# HV_Diffuser.net
KiCad netlist of a schematic drawn in Altium Designer
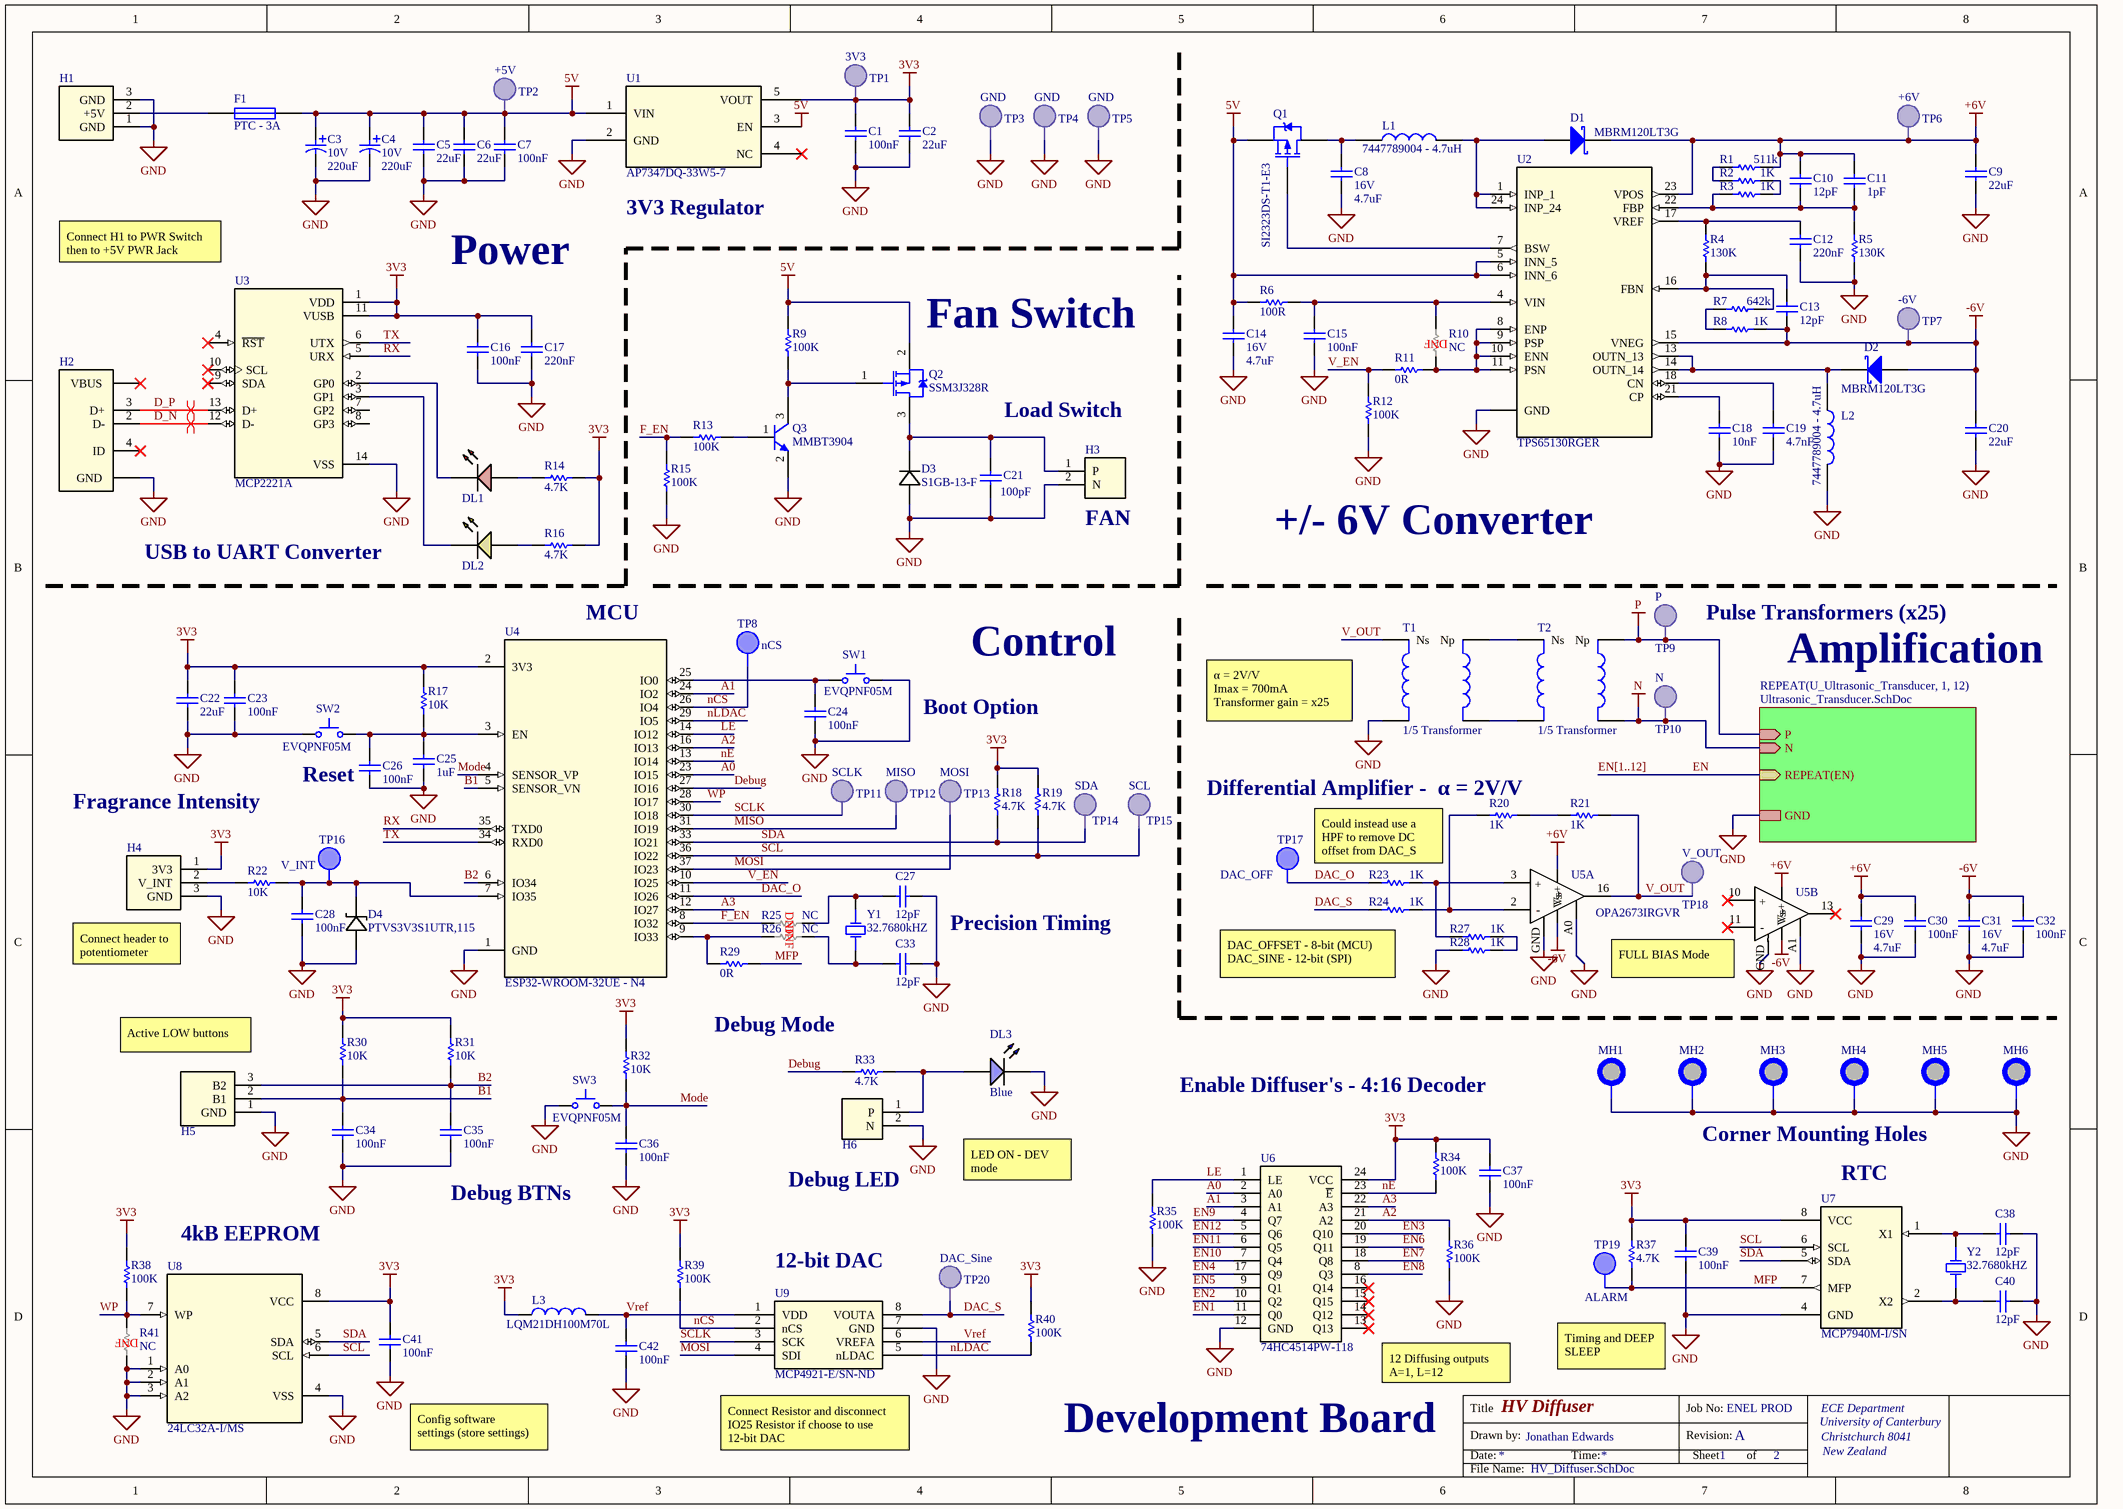
[diagram p0: HV_Diffuser.SchDoc]

(export (version "E")
  (design (tool "Eeschema 10.0.6"))
  (components
    (comp (ref "C1")
      (value "100nF")
      (footprint "C_0603")
      (description "CAP CER 0.1uF 50V X7R 0603")
      (libsource (lib "Diffuser") (part "CC_100nF"))
    )
    (comp (ref "C2")
      (value "22uF")
      (footprint "C_0805")
      (description "CAP CER 22UF 10V X5R 0805")
      (libsource (lib "Diffuser") (part "CC_22uF"))
    )
    (comp (ref "C3")
      (value "220uF")
      (footprint "C_2917")
      (description "100 µF Molded Tantalum Capacitors 16 V 2917 (7343 Metric) 75mOhm")
      (fields (field (name "VOLTAGE") "10V"))
      (libsource (lib "Diffuser") (part "CC_100uF"))
    )
    (comp (ref "C4")
      (value "220uF")
      (footprint "C_2917")
      (description "100 µF Molded Tantalum Capacitors 16 V 2917 (7343 Metric) 75mOhm")
      (fields (field (name "VOLTAGE") "10V"))
      (libsource (lib "Diffuser") (part "CC_100uF"))
    )
    (comp (ref "C5")
      (value "22uF")
      (footprint "C_0805")
      (description "CAP CER 22UF 10V X5R 0805")
      (libsource (lib "Diffuser") (part "CC_22uF"))
    )
    (comp (ref "C6")
      (value "22uF")
      (footprint "C_0805")
      (description "CAP CER 22UF 10V X5R 0805")
      (libsource (lib "Diffuser") (part "CC_22uF"))
    )
    (comp (ref "C7")
      (value "100nF")
      (footprint "C_0603")
      (description "CAP CER 0.1uF 50V X7R 0603")
      (libsource (lib "Diffuser") (part "CC_100nF"))
    )
    (comp (ref "C8")
      (value "4.7uF")
      (footprint "C_0805")
      (description "4.7 µF ±10% 50V Ceramic Capacitor X7R 0805 (2012 Metric)")
      (fields (field (name "VOLTAGE") "16V"))
      (libsource (lib "Diffuser") (part "CC_4.7uF_50V"))
    )
    (comp (ref "C9")
      (value "22uF")
      (footprint "C_0805")
      (description "CAP CER 22UF 10V X5R 0805")
      (libsource (lib "Diffuser") (part "CC_22uF"))
    )
    (comp (ref "C10")
      (value "12pF")
      (footprint "C_0603")
      (description "CAP CER 0.220uF 50V X7R 0603")
      (libsource (lib "Diffuser") (part "CC_220nF"))
    )
    (comp (ref "C11")
      (value "1pF")
      (footprint "C_0603")
      (description "CAP CER 1pF 50V X7R 0603")
      (libsource (lib "Diffuser") (part "CC_220nF"))
    )
    (comp (ref "C12")
      (value "220nF")
      (footprint "C_0603")
      (description "CAP CER 0.220uF 50V X7R 0603")
      (libsource (lib "Diffuser") (part "CC_220nF"))
    )
    (comp (ref "C13")
      (value "12pF")
      (footprint "C_0603")
      (description "CAP CER 0.220uF 50V X7R 0603")
      (libsource (lib "Diffuser") (part "CC_220nF"))
    )
    (comp (ref "C14")
      (value "4.7uF")
      (footprint "C_0805")
      (description "4.7 µF ±10% 50V Ceramic Capacitor X7R 0805 (2012 Metric)")
      (fields (field (name "VOLTAGE") "16V"))
      (libsource (lib "Diffuser") (part "CC_4.7uF_50V"))
    )
    (comp (ref "C15")
      (value "100nF")
      (footprint "C_0603")
      (description "CAP CER 0.1uF 50V X7R 0603")
      (libsource (lib "Diffuser") (part "CC_100nF"))
    )
    (comp (ref "C16")
      (value "100nF")
      (footprint "C_0603")
      (description "CAP CER 0.1uF 50V X7R 0603")
      (libsource (lib "Diffuser") (part "CC_100nF"))
    )
    (comp (ref "C17")
      (value "220nF")
      (footprint "C_0603")
      (description "CAP CER 0.220uF 50V X7R 0603")
      (libsource (lib "Diffuser") (part "CC_220nF"))
    )
    (comp (ref "C18")
      (value "10nF")
      (footprint "C_0603")
      (description "CAP CER 0.1uF 50V X7R 0603")
      (libsource (lib "Diffuser") (part "CC_100nF"))
    )
    (comp (ref "C19")
      (value "4.7nF")
      (footprint "C_0603")
      (description "CAP CER 4.7nF 50V X7R 0603")
      (libsource (lib "Diffuser") (part "CC_4.7nF"))
    )
    (comp (ref "C20")
      (value "22uF")
      (footprint "C_0805")
      (description "CAP CER 22UF 10V X5R 0805")
      (libsource (lib "Diffuser") (part "CC_22uF"))
    )
    (comp (ref "C21")
      (value "100pF")
      (footprint "C_0603")
      (description "CAP CER 100pF 50V C0G/NP0 0603")
      (fields (field (name "VOLTAGE") "50V"))
      (libsource (lib "Diffuser") (part "CC_100pF"))
    )
    (comp (ref "C22")
      (value "22uF")
      (footprint "C_0805")
      (description "CAP CER 22UF 10V X5R 0805")
      (libsource (lib "Diffuser") (part "CC_22uF"))
    )
    (comp (ref "C23")
      (value "100nF")
      (footprint "C_0603")
      (description "CAP CER 0.1uF 50V X7R 0603")
      (libsource (lib "Diffuser") (part "CC_100nF"))
    )
    (comp (ref "C24")
      (value "100nF")
      (footprint "C_0603")
      (description "CAP CER 0.1uF 50V X7R 0603")
      (libsource (lib "Diffuser") (part "CC_100nF"))
    )
    (comp (ref "C25")
      (value "1uF")
      (footprint "C_0603")
      (description "CAP CER 1uF 16V X7R 0603")
      (libsource (lib "Diffuser") (part "CC_1uF"))
    )
    (comp (ref "C26")
      (value "100nF")
      (footprint "C_0603")
      (description "CAP CER 0.1uF 50V X7R 0603")
      (libsource (lib "Diffuser") (part "CC_100nF"))
    )
    (comp (ref "C27")
      (value "12pF")
      (footprint "C_0603")
      (description "CAP CER 0.220uF 50V X7R 0603")
      (libsource (lib "Diffuser") (part "CC_220nF"))
    )
    (comp (ref "C28")
      (value "100nF")
      (footprint "C_0603")
      (description "CAP CER 0.1uF 50V X7R 0603")
      (libsource (lib "Diffuser") (part "CC_100nF"))
    )
    (comp (ref "C29")
      (value "4.7uF")
      (footprint "C_0805")
      (description "4.7 µF ±10% 50V Ceramic Capacitor X7R 0805 (2012 Metric)")
      (fields (field (name "VOLTAGE") "16V"))
      (libsource (lib "Diffuser") (part "CC_4.7uF_50V"))
    )
    (comp (ref "C30")
      (value "100nF")
      (footprint "C_0603")
      (description "CAP CER 0.1uF 50V X7R 0603")
      (libsource (lib "Diffuser") (part "CC_100nF"))
    )
    (comp (ref "C31")
      (value "4.7uF")
      (footprint "C_0805")
      (description "4.7 µF ±10% 50V Ceramic Capacitor X7R 0805 (2012 Metric)")
      (fields (field (name "VOLTAGE") "16V"))
      (libsource (lib "Diffuser") (part "CC_4.7uF_50V"))
    )
    (comp (ref "C32")
      (value "100nF")
      (footprint "C_0603")
      (description "CAP CER 0.1uF 50V X7R 0603")
      (libsource (lib "Diffuser") (part "CC_100nF"))
    )
    (comp (ref "C33")
      (value "12pF")
      (footprint "C_0603")
      (description "CAP CER 0.220uF 50V X7R 0603")
      (libsource (lib "Diffuser") (part "CC_220nF"))
    )
    (comp (ref "C34")
      (value "100nF")
      (footprint "C_0603")
      (description "CAP CER 0.1uF 50V X7R 0603")
      (libsource (lib "Diffuser") (part "CC_100nF"))
    )
    (comp (ref "C35")
      (value "100nF")
      (footprint "C_0603")
      (description "CAP CER 0.1uF 50V X7R 0603")
      (libsource (lib "Diffuser") (part "CC_100nF"))
    )
    (comp (ref "C36")
      (value "100nF")
      (footprint "C_0603")
      (description "CAP CER 0.1uF 50V X7R 0603")
      (libsource (lib "Diffuser") (part "CC_100nF"))
    )
    (comp (ref "C37")
      (value "100nF")
      (footprint "C_0603")
      (description "CAP CER 0.1uF 50V X7R 0603")
      (libsource (lib "Diffuser") (part "CC_100nF"))
    )
    (comp (ref "C38")
      (value "12pF")
      (footprint "C_0603")
      (description "CAP CER 0.220uF 50V X7R 0603")
      (libsource (lib "Diffuser") (part "CC_220nF"))
    )
    (comp (ref "C39")
      (value "100nF")
      (footprint "C_0603")
      (description "CAP CER 0.1uF 50V X7R 0603")
      (libsource (lib "Diffuser") (part "CC_100nF"))
    )
    (comp (ref "C40")
      (value "12pF")
      (footprint "C_0603")
      (description "CAP CER 0.220uF 50V X7R 0603")
      (libsource (lib "Diffuser") (part "CC_220nF"))
    )
    (comp (ref "C41")
      (value "100nF")
      (footprint "C_0603")
      (description "CAP CER 0.1uF 50V X7R 0603")
      (libsource (lib "Diffuser") (part "CC_100nF"))
    )
    (comp (ref "C42")
      (value "100nF")
      (footprint "C_0603")
      (description "CAP CER 0.1uF 50V X7R 0603")
      (libsource (lib "Diffuser") (part "CC_100nF"))
    )
    (comp (ref "D1")
      (value "MBRM120LT3G")
      (footprint "DO-216AA")
      (description "Diode 20 V 1A Surface Mount Powermite")
      (fields (field (name "COPYRIGHT") "Copyright (C) 2024 Ultra Librarian. All rights reserved."))
      (libsource (lib "Diffuser") (part "MBRM120LT3G"))
    )
    (comp (ref "D2")
      (value "MBRM120LT3G")
      (footprint "DO-216AA")
      (description "Diode 20 V 1A Surface Mount Powermite")
      (fields (field (name "COPYRIGHT") "Copyright (C) 2024 Ultra Librarian. All rights reserved."))
      (libsource (lib "Diffuser") (part "MBRM120LT3G"))
    )
    (comp (ref "D3")
      (value "S1GB-13-F")
      (footprint "DO-214AA, SMB")
      (description "Diode 400 V 1A Surface Mount SMB")
      (libsource (lib "Diffuser") (part "S1GB-13-F"))
    )
    (comp (ref "D4")
      (value "PTVS3V3S1UTR,115")
      (footprint "CR_PTVS3V_NEX-M")
      (description "8V Clamp 43.8A Ipp Tvs Diode Surface Mount SOD-123W")
      (fields (field (name "COPYRIGHT") "Copyright (C) 2023 Ultra Librarian. All rights reserved."))
      (libsource (lib "Diffuser") (part "PTVS3V3S1UTR,115"))
    )
    (comp (ref "DL1")
      (value "Red")
      (footprint "WL-SMCW0603")
      (description "LED Red 250mcd 0603 SMD")
      (libsource (lib "Diffuser") (part "Leds - 150060RS75000"))
    )
    (comp (ref "DL2")
      (value "Yellow")
      (footprint "WL-SMCW0603")
      (description "LED Yellow 120mcd 0603 SMD")
      (libsource (lib "Diffuser") (part "Leds - 150060YS75000"))
    )
    (comp (ref "DL3")
      (value "Blue")
      (footprint "WL-SMCW0603")
      (description "LED Blue 270mcd 0603 SMD")
      (fields (field (name "LED COLOUR") "Blue"))
      (libsource (lib "Diffuser") (part "Leds - 150060BS75000"))
    )
    (comp (ref "F1")
      (value "PTC - 3A")
      (footprint "PTC_Fuse_1812")
      (description "PTC RESET FUSE 3.0A 24V 1812")
      (libsource (lib "Diffuser") (part "FS_PTC_Fuse_3A"))
    )
    (comp (ref "H1")
      (value "3 pin - 2mm")
      (footprint "TE_440054-3")
      (description "2.0MM,HDR,3POS,VERTICAL")
      (fields (field (name "MP") "440054-3") (field (name "MF") "TE Connectivity"))
      (libsource (lib "Diffuser") (part "440054-3"))
    )
    (comp (ref "H2")
      (value "JS_USB_MICRO_B")
      (footprint "JS_USB_MICRO_B")
      (description "CONN USB MICRO B RECPT SMT R/A")
      (fields (field (name "MANUFACTURER") "FCI") (field (name "MANUFACTURER PART NUMBER") "10118194-0001LF"))
      (libsource (lib "Diffuser") (part "JS_USB_MICRO_B_SMT"))
    )
    (comp (ref "H3")
      (value "2 Pin Male 2mm")
      (footprint "JST_B2B-PH-K-S")
      (description "CONN HDR 2POS 0.1 TIN PCB")
      (libsource (lib "") (part "2 Pin Male 2mm_1"))
    )
    (comp (ref "H4")
      (value "3 pin - 2mm")
      (footprint "TE_440054-3")
      (description "2.0MM,HDR,3POS,VERTICAL")
      (fields (field (name "MP") "440054-3") (field (name "MF") "TE Connectivity"))
      (libsource (lib "") (part "440054-3_1"))
    )
    (comp (ref "H5")
      (value "3 pin - 2mm")
      (footprint "TE_440054-3")
      (description "2.0MM,HDR,3POS,VERTICAL")
      (fields (field (name "MP") "440054-3") (field (name "MF") "TE Connectivity"))
      (libsource (lib "Diffuser") (part "440054-3"))
    )
    (comp (ref "H6")
      (value "2 Pin Male 2mm")
      (footprint "JST_B2B-PH-K-S")
      (description "CONN HDR 2POS 0.1 TIN PCB")
      (libsource (lib "Diffuser") (part "2 Pin Male 2mm"))
    )
    (comp (ref "L1")
      (value "7447789004 - 4.7uH")
      (footprint "7447789004 - 4.7uH")
      (description "4.7 µH Shielded Drum Core, Wirewound Inductor 2.9 A 35mOhm Max Nonstandard")
      (libsource (lib "Diffuser") (part "7447789004 - 4.7uH"))
    )
    (comp (ref "L2")
      (value "7447789004 - 4.7uH")
      (footprint "7447789004 - 4.7uH")
      (description "4.7 µH Shielded Drum Core, Wirewound Inductor 2.9 A 35mOhm Max Nonstandard")
      (libsource (lib "") (part "7447789004 - 4.7uH_1"))
    )
    (comp (ref "L3")
      (value "LQM21DH100M70L")
      (footprint "R_0805")
      (description "Inductor with Inductance: 10uH Tol. +/-20%, Package: 0805 (2012)")
      (libsource (lib "Diffuser") (part "10uH - LQM21DH100M70L"))
    )
    (comp (ref "MH1")
      (value "MH_M2")
      (footprint "MH_M2")
      (description "Mounting Holes")
      (libsource (lib "Diffuser") (part "MH_M2"))
    )
    (comp (ref "MH2")
      (value "MH_M2")
      (footprint "MH_M2")
      (description "Mounting Holes")
      (libsource (lib "Diffuser") (part "MH_M2"))
    )
    (comp (ref "MH3")
      (value "MH_M2")
      (footprint "MH_M2")
      (description "Mounting Holes")
      (libsource (lib "Diffuser") (part "MH_M2"))
    )
    (comp (ref "MH4")
      (value "MH_M2")
      (footprint "MH_M2")
      (description "Mounting Holes")
      (libsource (lib "Diffuser") (part "MH_M2"))
    )
    (comp (ref "MH5")
      (value "MH_M2")
      (footprint "MH_M2")
      (description "Mounting Holes")
      (libsource (lib "Diffuser") (part "MH_M2"))
    )
    (comp (ref "MH6")
      (value "MH_M2")
      (footprint "MH_M2")
      (description "Mounting Holes")
      (libsource (lib "Diffuser") (part "MH_M2"))
    )
    (comp (ref "Q1")
      (value "SI2323DS-T1-E3")
      (footprint "SOT23")
      (description "P-Channel 20V 3.7A _Ta_ 750mW _Ta_ Surface Mount SOT-23-3 _TO-236_")
      (fields (field (name "MF") "Vishay Siliconix"))
      (libsource (lib "Diffuser") (part "SI2323DS-T1-E3"))
    )
    (comp (ref "Q2")
      (value "SSM3J328R")
      (footprint "SOT-23F")
      (description "MOSFET P-CH 20V 6A SOT23F")
      (libsource (lib "Diffuser") (part "P Mos - SSM3J328R"))
    )
    (comp (ref "Q3")
      (value "MMBT3904")
      (footprint "SOT23_NXP-M")
      (description "TRANS NPN 40V 200MA TO236AB")
      (fields (field (name "MANUFACTURER") "NXP"))
      (libsource (lib "Diffuser") (part "NPN - MMBT3904"))
    )
    (comp (ref "R1")
      (value "511k")
      (footprint "R_0603")
      (description "RES 512K OHM 0.1% 1/10W 0603")
      (libsource (lib "Diffuser") (part "RS_100K"))
    )
    (comp (ref "R2")
      (value "1K")
      (footprint "R_0603")
      (description "RES 1K OHM 0.1% 1/10W 0603")
      (libsource (lib "Diffuser") (part "RS_1K"))
    )
    (comp (ref "R3")
      (value "1K")
      (footprint "R_0603")
      (description "RES 1K OHM 0.1% 1/10W 0603")
      (libsource (lib "Diffuser") (part "RS_1K"))
    )
    (comp (ref "R4")
      (value "130K")
      (footprint "R_0603")
      (description "RES 130K OHM 0.1% 1/10W 0603")
      (libsource (lib "Diffuser") (part "RS_1K"))
    )
    (comp (ref "R5")
      (value "130K")
      (footprint "R_0603")
      (description "RES 130K OHM 0.1% 1/10W 0603")
      (libsource (lib "Diffuser") (part "RS_1K"))
    )
    (comp (ref "R6")
      (value "100R")
      (footprint "R_0603")
      (description "100 Ohms ±0.1% 0.167W, 1/6W Chip Resistor 0603 (1608 Metric) Thin Film")
      (libsource (lib "Diffuser") (part "RS_0R"))
    )
    (comp (ref "R7")
      (value "642k")
      (footprint "R_0603")
      (description "RES 100K OHM 1% 1/10W 0603")
      (libsource (lib "Diffuser") (part "RS_100K"))
    )
    (comp (ref "R8")
      (value "1K")
      (footprint "R_0603")
      (description "RES 1K OHM 0.1% 1/10W 0603")
      (libsource (lib "Diffuser") (part "RS_1K"))
    )
    (comp (ref "R9")
      (value "100K")
      (footprint "R_0603")
      (description "RES 100K OHM 1% 1/10W 0603")
      (libsource (lib "Diffuser") (part "RS_100K"))
    )
    (comp (ref "R10")
      (value "NC")
      (footprint "R_0603_NC")
      (description "NC - 0603")
      (libsource (lib "Diffuser") (part "RS_NC"))
    )
    (comp (ref "R11")
      (value "0R")
      (footprint "R_0603")
      (description "RES SMD 0 OHM JUMPER 1/10W 0603")
      (libsource (lib "Diffuser") (part "RS_0R"))
    )
    (comp (ref "R12")
      (value "100K")
      (footprint "R_0603")
      (description "RES 100K OHM 1% 1/10W 0603")
      (libsource (lib "Diffuser") (part "RS_100K"))
    )
    (comp (ref "R13")
      (value "100K")
      (footprint "R_0603")
      (description "RES 100K OHM 1% 1/10W 0603")
      (libsource (lib "Diffuser") (part "RS_100K"))
    )
    (comp (ref "R14")
      (value "4.7K")
      (footprint "R_0603")
      (description "RES SMD 4.7K OHM 1% 1/10W 0603")
      (libsource (lib "Diffuser") (part "RS_4.7K"))
    )
    (comp (ref "R15")
      (value "100K")
      (footprint "R_0603")
      (description "RES 100K OHM 1% 1/10W 0603")
      (libsource (lib "Diffuser") (part "RS_100K"))
    )
    (comp (ref "R16")
      (value "4.7K")
      (footprint "R_0603")
      (description "RES SMD 4.7K OHM 1% 1/10W 0603")
      (libsource (lib "Diffuser") (part "RS_4.7K"))
    )
    (comp (ref "R17")
      (value "10K")
      (footprint "R_0603")
      (description "RES SMD 10K OHM 1% 1/10W 0603")
      (libsource (lib "Diffuser") (part "RS_10K"))
    )
    (comp (ref "R18")
      (value "4.7K")
      (footprint "R_0603")
      (description "RES SMD 4.7K OHM 1% 1/10W 0603")
      (libsource (lib "Diffuser") (part "RS_4.7K"))
    )
    (comp (ref "R19")
      (value "4.7K")
      (footprint "R_0603")
      (description "RES SMD 4.7K OHM 1% 1/10W 0603")
      (libsource (lib "Diffuser") (part "RS_4.7K"))
    )
    (comp (ref "R20")
      (value "1K")
      (footprint "R_0603")
      (description "RES 1K OHM 1% 1/10W 0603")
      (libsource (lib "Diffuser") (part "RS_1K"))
    )
    (comp (ref "R21")
      (value "1K")
      (footprint "R_0603")
      (description "RES 1K OHM 1% 1/10W 0603")
      (libsource (lib "Diffuser") (part "RS_1K"))
    )
    (comp (ref "R22")
      (value "10K")
      (footprint "R_0603")
      (description "RES SMD 10K OHM 1% 1/10W 0603")
      (libsource (lib "Diffuser") (part "RS_10K"))
    )
    (comp (ref "R23")
      (value "1K")
      (footprint "R_0603")
      (description "RES 1K OHM 1% 1/10W 0603")
      (libsource (lib "Diffuser") (part "RS_1K"))
    )
    (comp (ref "R24")
      (value "1K")
      (footprint "R_0603")
      (description "RES 1K OHM 1% 1/10W 0603")
      (libsource (lib "Diffuser") (part "RS_1K"))
    )
    (comp (ref "R25")
      (value "NC")
      (footprint "R_0603_NC")
      (description "NC - 0603")
      (libsource (lib "Diffuser") (part "RS_NC"))
    )
    (comp (ref "R26")
      (value "NC")
      (footprint "R_0603_NC")
      (description "NC - 0603")
      (libsource (lib "Diffuser") (part "RS_NC"))
    )
    (comp (ref "R27")
      (value "1K")
      (footprint "R_0603")
      (description "RES 1K OHM 1% 1/10W 0603")
      (libsource (lib "Diffuser") (part "RS_1K"))
    )
    (comp (ref "R28")
      (value "1K")
      (footprint "R_0603")
      (description "RES 1K OHM 1% 1/10W 0603")
      (libsource (lib "Diffuser") (part "RS_1K"))
    )
    (comp (ref "R29")
      (value "0R")
      (footprint "R_0603")
      (description "RES SMD 0 OHM JUMPER 1/10W 0603")
      (libsource (lib "Diffuser") (part "RS_0R"))
    )
    (comp (ref "R30")
      (value "10K")
      (footprint "R_0603")
      (description "RES SMD 10K OHM 1% 1/10W 0603")
      (libsource (lib "Diffuser") (part "RS_10K"))
    )
    (comp (ref "R31")
      (value "10K")
      (footprint "R_0603")
      (description "RES SMD 10K OHM 1% 1/10W 0603")
      (libsource (lib "Diffuser") (part "RS_10K"))
    )
    (comp (ref "R32")
      (value "10K")
      (footprint "R_0603")
      (description "RES SMD 10K OHM 1% 1/10W 0603")
      (libsource (lib "Diffuser") (part "RS_10K"))
    )
    (comp (ref "R33")
      (value "4.7K")
      (footprint "R_0603")
      (description "RES SMD 4.7K OHM 1% 1/10W 0603")
      (libsource (lib "Diffuser") (part "RS_4.7K"))
    )
    (comp (ref "R34")
      (value "100K")
      (footprint "R_0603")
      (description "RES 100K OHM 1% 1/10W 0603")
      (libsource (lib "Diffuser") (part "RS_100K"))
    )
    (comp (ref "R35")
      (value "100K")
      (footprint "R_0603")
      (description "RES 100K OHM 1% 1/10W 0603")
      (libsource (lib "Diffuser") (part "RS_100K"))
    )
    (comp (ref "R36")
      (value "100K")
      (footprint "R_0603")
      (description "RES 100K OHM 1% 1/10W 0603")
      (libsource (lib "Diffuser") (part "RS_100K"))
    )
    (comp (ref "R37")
      (value "4.7K")
      (footprint "R_0603")
      (description "RES SMD 4.7K OHM 1% 1/10W 0603")
      (libsource (lib "Diffuser") (part "RS_4.7K"))
    )
    (comp (ref "R38")
      (value "100K")
      (footprint "R_0603")
      (description "RES 100K OHM 1% 1/10W 0603")
      (libsource (lib "Diffuser") (part "RS_100K"))
    )
    (comp (ref "R39")
      (value "100K")
      (footprint "R_0603")
      (description "RES 100K OHM 1% 1/10W 0603")
      (libsource (lib "Diffuser") (part "RS_100K"))
    )
    (comp (ref "R40")
      (value "100K")
      (footprint "R_0603")
      (description "RES 100K OHM 1% 1/10W 0603")
      (libsource (lib "Diffuser") (part "RS_100K"))
    )
    (comp (ref "R41")
      (value "NC")
      (footprint "R_0603_NC")
      (description "NC - 0603")
      (libsource (lib "Diffuser") (part "RS_NC"))
    )
    (comp (ref "SW1")
      (value "EVQPNF05M")
      (footprint "Tactile Switche - EVQPNF05M")
      (description "Panasonic 6 x 3.5mm SMD Light Touch Switch Type SMD")
      (fields (field (name "MANUFACTURER") "Panasonic"))
      (libsource (lib "Diffuser") (part "Tactile Switch - WS_EVQPNF05M"))
    )
    (comp (ref "SW2")
      (value "EVQPNF05M")
      (footprint "Tactile Switche - EVQPNF05M")
      (description "Panasonic 6 x 3.5mm SMD Light Touch Switch Type SMD")
      (fields (field (name "MANUFACTURER") "Panasonic"))
      (libsource (lib "Diffuser") (part "Tactile Switch - WS_EVQPNF05M"))
    )
    (comp (ref "SW3")
      (value "EVQPNF05M")
      (footprint "Tactile Switche - EVQPNF05M")
      (description "Panasonic 6 x 3.5mm SMD Light Touch Switch Type SMD")
      (fields (field (name "MANUFACTURER") "Panasonic"))
      (libsource (lib "Diffuser") (part "Tactile Switch - WS_EVQPNF05M"))
    )
    (comp (ref "T1")
      (value "1/5 Transformer")
      (footprint "PMT9085NL")
      (description "160µH Gate Drive Pulse Transformer 1CT:5CT Surface Mount")
      (libsource (lib "Diffuser") (part "PMT9085NL"))
    )
    (comp (ref "T2")
      (value "1/5 Transformer")
      (footprint "PMT9085NL")
      (description "160µH Gate Drive Pulse Transformer 1CT:5CT Surface Mount")
      (libsource (lib "Diffuser") (part "PMT9085NL"))
    )
    (comp (ref "TP1")
      (value "3V3")
      (footprint "TP_1206")
      (description "TP, 325mm x 1.65mm)")
      (fields
        (field (name "MANUFACTURER") "Harwin Inc")
        (field (name "MANUFACTURER PART NUMBER") "S1751-46R")
      )
      (libsource (lib "Diffuser") (part "TP_1206"))
    )
    (comp (ref "TP2")
      (value "+5V")
      (footprint "TP_1206")
      (description "TP, 325mm x 1.65mm)")
      (fields
        (field (name "MANUFACTURER") "Harwin Inc")
        (field (name "MANUFACTURER PART NUMBER") "S1751-46R")
      )
      (libsource (lib "Diffuser") (part "TP_1206"))
    )
    (comp (ref "TP3")
      (value "GND")
      (footprint "TP_1206")
      (description "TP, 325mm x 1.65mm)")
      (fields
        (field (name "MANUFACTURER") "Harwin Inc")
        (field (name "MANUFACTURER PART NUMBER") "S1751-46R")
      )
      (libsource (lib "Diffuser") (part "TP_1206"))
    )
    (comp (ref "TP4")
      (value "GND")
      (footprint "TP_1206")
      (description "TP, 325mm x 1.65mm)")
      (fields
        (field (name "MANUFACTURER") "Harwin Inc")
        (field (name "MANUFACTURER PART NUMBER") "S1751-46R")
      )
      (libsource (lib "Diffuser") (part "TP_1206"))
    )
    (comp (ref "TP5")
      (value "GND")
      (footprint "TP_1206")
      (description "TP, 325mm x 1.65mm)")
      (fields
        (field (name "MANUFACTURER") "Harwin Inc")
        (field (name "MANUFACTURER PART NUMBER") "S1751-46R")
      )
      (libsource (lib "Diffuser") (part "TP_1206"))
    )
    (comp (ref "TP6")
      (value "+6V")
      (footprint "TP_1206")
      (description "TP, 325mm x 1.65mm)")
      (fields
        (field (name "MANUFACTURER") "Harwin Inc")
        (field (name "MANUFACTURER PART NUMBER") "S1751-46R")
      )
      (libsource (lib "Diffuser") (part "TP_1206"))
    )
    (comp (ref "TP7")
      (value "-6V")
      (footprint "TP_1206")
      (description "TP, 325mm x 1.65mm)")
      (fields
        (field (name "MANUFACTURER") "Harwin Inc")
        (field (name "MANUFACTURER PART NUMBER") "S1751-46R")
      )
      (libsource (lib "Diffuser") (part "TP_1206"))
    )
    (comp (ref "TP8")
      (value "nCS")
      (footprint "TP-Small")
      (description "Use for basic signals")
      (libsource (lib "Diffuser") (part "TP-Small"))
    )
    (comp (ref "TP9")
      (value "P")
      (footprint "TP_1206")
      (description "TP, 325mm x 1.65mm)")
      (fields
        (field (name "MANUFACTURER") "Harwin Inc")
        (field (name "MANUFACTURER PART NUMBER") "S1751-46R")
      )
      (libsource (lib "Diffuser") (part "TP_1206"))
    )
    (comp (ref "TP10")
      (value "N")
      (footprint "TP_1206")
      (description "TP, 325mm x 1.65mm)")
      (fields
        (field (name "MANUFACTURER") "Harwin Inc")
        (field (name "MANUFACTURER PART NUMBER") "S1751-46R")
      )
      (libsource (lib "Diffuser") (part "TP_1206"))
    )
    (comp (ref "TP11")
      (value "SCLK")
      (footprint "TP_1206")
      (description "TP, 325mm x 1.65mm)")
      (fields
        (field (name "MANUFACTURER") "Harwin Inc")
        (field (name "MANUFACTURER PART NUMBER") "S1751-46R")
      )
      (libsource (lib "Diffuser") (part "TP_1206"))
    )
    (comp (ref "TP12")
      (value "MISO")
      (footprint "TP_1206")
      (description "TP, 325mm x 1.65mm)")
      (fields
        (field (name "MANUFACTURER") "Harwin Inc")
        (field (name "MANUFACTURER PART NUMBER") "S1751-46R")
      )
      (libsource (lib "Diffuser") (part "TP_1206"))
    )
    (comp (ref "TP13")
      (value "MOSI")
      (footprint "TP_1206")
      (description "TP, 325mm x 1.65mm)")
      (fields
        (field (name "MANUFACTURER") "Harwin Inc")
        (field (name "MANUFACTURER PART NUMBER") "S1751-46R")
      )
      (libsource (lib "Diffuser") (part "TP_1206"))
    )
    (comp (ref "TP14")
      (value "SDA")
      (footprint "TP_1206")
      (description "TP, 325mm x 1.65mm)")
      (fields
        (field (name "MANUFACTURER") "Harwin Inc")
        (field (name "MANUFACTURER PART NUMBER") "S1751-46R")
      )
      (libsource (lib "Diffuser") (part "TP_1206"))
    )
    (comp (ref "TP15")
      (value "SCL")
      (footprint "TP_1206")
      (description "TP, 325mm x 1.65mm)")
      (fields
        (field (name "MANUFACTURER") "Harwin Inc")
        (field (name "MANUFACTURER PART NUMBER") "S1751-46R")
      )
      (libsource (lib "Diffuser") (part "TP_1206"))
    )
    (comp (ref "TP16")
      (value "V_INT")
      (footprint "TP-Small")
      (description "Use for basic signals")
      (libsource (lib "Diffuser") (part "TP-Small"))
    )
    (comp (ref "TP17")
      (value "DAC_OFF")
      (footprint "TP-Small")
      (description "Use for basic signals")
      (libsource (lib "Diffuser") (part "TP-Small"))
    )
    (comp (ref "TP18")
      (value "V_OUT")
      (footprint "TP_1206")
      (description "TP, 325mm x 1.65mm)")
      (fields
        (field (name "MANUFACTURER") "Harwin Inc")
        (field (name "MANUFACTURER PART NUMBER") "S1751-46R")
      )
      (libsource (lib "Diffuser") (part "TP_1206"))
    )
    (comp (ref "TP19")
      (value "ALARM")
      (footprint "TP-Small")
      (description "Use for basic signals")
      (libsource (lib "Diffuser") (part "TP-Small"))
    )
    (comp (ref "TP20")
      (value "DAC_Sine")
      (footprint "TP_1206")
      (description "TP, 325mm x 1.65mm)")
      (fields
        (field (name "MANUFACTURER") "Harwin Inc")
        (field (name "MANUFACTURER PART NUMBER") "S1751-46R")
      )
      (libsource (lib "Diffuser") (part "TP_1206"))
    )
    (comp (ref "U1")
      (value "AP7347DQ-33W5-7")
      (footprint "SOT25-A1_DIO-M")
      (description "Linear Voltage Regulator IC Positive Fixed 1 Output 500mA SOT-25")
      (fields (field (name "COPYRIGHT") "Copyright (C) 2024 Ultra Librarian. All rights reserved."))
      (libsource (lib "Diffuser") (part "AP7347DQ-33W5-7"))
    )
    (comp (ref "U2")
      (value "TPS65130RGER")
      (footprint "QFN50P400X400X100-25N")
      (libsource (lib "Diffuser") (part "TPS65130RGER"))
    )
    (comp (ref "U3")
      (value "MCP2221A")
      (footprint "14-SOIC")
      (description "USB Bridge, USB to I2C/UART USB 2.0 I2C, UART Interface 14-SOIC")
      (libsource (lib "Diffuser") (part "USB Serial - MCP2221A-I/ST"))
    )
    (comp (ref "U4")
      (value "ESP32-WROOM-32UE - N4")
      (footprint "MODULE_ESP32-WROOM-32UE(M113EH6400UH3Q0)")
      (fields (field (name "MF") "Espressif Systems") (field (name "MP") "ESP32-WROOM-32UE(M113EH6400UH3Q0)"))
      (libsource (lib "Diffuser") (part "ESP32-WROOM-32UE(M113EH6400UH3Q0)"))
    )
    (comp (ref "U5")
      (value "OPA2673IRGVR")
      (footprint "RGV16_2P16X2P16")
      (description "Current Feedback Amplifier 2 Circuit 16-VQFN (4x4)")
      (fields (field (name "COPYRIGHT") "Copyright (C) 2024 Ultra Librarian. All rights reserved."))
      (libsource (lib "Diffuser") (part "OPA2673IRGVR"))
    )
    (comp (ref "U6")
      (value "74HC4514PW-118")
      (footprint "SOP65P640X110-24N")
      (description "74HC(T)4514 - 4-to-16 line decoder/demultiplexer with input latches@en-us")
      (fields
        (field (name "MOUSER PART NUMBER") "771-HC4514PW118")
        (field (name "MANUFACTURER_PART_NUMBER") "74HC4514PW,118")
      )
      (libsource (lib "Diffuser") (part "74HC4514PW-118"))
    )
    (comp (ref "U7")
      (value "MCP7940M-I/SN")
      (footprint "SOIC8-N_MC_MCH")
      (description "Real Time Clock (RTC) IC Clock/Calendar 64B I2C, 2-Wire Serial 8-SOIC (0.154\", 3.90mm Width)")
      (fields (field (name "COPYRIGHT") "Copyright (C) 2024 Ultra Librarian. All rights reserved."))
      (libsource (lib "Diffuser") (part "MCP7940M-ISN"))
    )
    (comp (ref "U8")
      (value "24LC32A-I/MS")
      (footprint "SOP65P490X110-8N")
      (description "EEPROM Memory IC 32Kb _4K x 8_ IÂ²C 400kHz 900ns 8-MSOP")
      (fields (field (name "MF") "Microchip"))
      (libsource (lib "Diffuser") (part "24LC32A-I/MS"))
    )
    (comp (ref "U9")
      (value "MCP4921-E/SN-ND")
      (footprint "8-SOIC - DAC")
      (description "12 Bit Digital to Analog Converter 1 8-SOIC")
      (fields
        (field (name "MANUFACTURER_PART_NUMBER") "MCP4822T-E/SN")
        (field (name "COPYRIGHT") "Copyright (C) 2024 Ultra Librarian. All rights reserved.")
      )
      (libsource (lib "Diffuser") (part "MCP4921"))
    )
    (comp (ref "Y1")
      (value "32.7680kHZ")
      (footprint "XTAL_MS1V-T1K-32.768KHZ-9PF-20PPM-TA-QC-AU")
      (description "32.768 kHz ±20ppm Crystal 9pF 60 kOhms Cylindrical Can, Radial")
      (fields
        (field (name "MP") "MS1V-T1K-32.768KHZ-9PF-20PPM-TA-QC-AU")
        (field (name "MF") "Micro Crystal AG")
      )
      (libsource (lib "Diffuser") (part "32.7680kHZ"))
    )
    (comp (ref "Y2")
      (value "32.7680kHZ")
      (footprint "XTAL_MS1V-T1K-32.768KHZ-9PF-20PPM-TA-QC-AU")
      (description "32.768 kHz ±20ppm Crystal 9pF 60 kOhms Cylindrical Can, Radial")
      (fields
        (field (name "MP") "MS1V-T1K-32.768KHZ-9PF-20PPM-TA-QC-AU")
        (field (name "MF") "Micro Crystal AG")
      )
      (libsource (lib "Diffuser") (part "32.7680kHZ"))
    )
  )
  (nets
    (net (code "1") (name "+6V") (class "Default")
      (node (ref "C10") (pin "2") (pinfunction "2_2") (pintype "passive"))
      (node (ref "C11") (pin "2") (pinfunction "2_2") (pintype "passive"))
      (node (ref "C29") (pin "2") (pinfunction "2_2") (pintype "passive"))
      (node (ref "C30") (pin "2") (pinfunction "2_2") (pintype "passive"))
      (node (ref "C9") (pin "2") (pinfunction "2_2") (pintype "passive"))
      (node (ref "D1") (pin "1") (pinfunction "K_1") (pintype "passive"))
      (node (ref "R1") (pin "1") (pinfunction "1_1") (pintype "passive"))
      (node (ref "TP6") (pin "1") (pinfunction "1_1") (pintype "passive"))
      (node (ref "U2") (pin "23") (pinfunction "VPOS_23") (pintype "output"))
      (node (ref "U5") (pin "14") (pinfunction "Vs+_14") (pintype "power_in"))
    )
    (net (code "2") (name "-6V") (class "Default")
      (node (ref "C13") (pin "1") (pinfunction "1_1") (pintype "passive"))
      (node (ref "C20") (pin "2") (pinfunction "2_2") (pintype "passive"))
      (node (ref "C31") (pin "2") (pinfunction "2_2") (pintype "passive"))
      (node (ref "C32") (pin "2") (pinfunction "2_2") (pintype "passive"))
      (node (ref "D2") (pin "2") (pinfunction "A_2") (pintype "passive"))
      (node (ref "R8") (pin "1") (pinfunction "1_1") (pintype "passive"))
      (node (ref "TP7") (pin "1") (pinfunction "1_1") (pintype "passive"))
      (node (ref "U2") (pin "15") (pinfunction "VNEG_15") (pintype "output"))
      (node (ref "U5") (pin "7") (pinfunction "Vs-_7") (pintype "power_in"))
    )
    (net (code "3") (name "/A0") (class "Default")
      (node (ref "U4") (pin "23") (pinfunction "IO15_23") (pintype "bidirectional"))
      (node (ref "U6") (pin "2") (pinfunction "A0_2") (pintype "passive"))
    )
    (net (code "4") (name "/A1") (class "Default")
      (node (ref "U4") (pin "24") (pinfunction "IO2_24") (pintype "bidirectional"))
      (node (ref "U6") (pin "3") (pinfunction "A1_3") (pintype "passive"))
    )
    (net (code "5") (name "/A2") (class "Default")
      (node (ref "R36") (pin "2") (pinfunction "2_2") (pintype "passive"))
      (node (ref "U4") (pin "16") (pinfunction "IO13_16") (pintype "bidirectional"))
      (node (ref "U6") (pin "21") (pinfunction "A2_21") (pintype "passive"))
    )
    (net (code "6") (name "/A3") (class "Default")
      (node (ref "U4") (pin "12") (pinfunction "IO27_12") (pintype "bidirectional"))
      (node (ref "U6") (pin "22") (pinfunction "A3_22") (pintype "passive"))
    )
    (net (code "7") (name "/B1") (class "Default")
      (node (ref "C34") (pin "2") (pinfunction "2_2") (pintype "passive"))
      (node (ref "H5") (pin "2") (pinfunction "+5V_2") (pintype "passive"))
      (node (ref "R30") (pin "1") (pinfunction "1_1") (pintype "passive"))
      (node (ref "U4") (pin "5") (pinfunction "SENSOR_VN_5") (pintype "input"))
    )
    (net (code "8") (name "/B2") (class "Default")
      (node (ref "C35") (pin "2") (pinfunction "2_2") (pintype "passive"))
      (node (ref "H5") (pin "3") (pinfunction "GND_3") (pintype "passive"))
      (node (ref "R31") (pin "1") (pinfunction "1_1") (pintype "passive"))
      (node (ref "U4") (pin "6") (pinfunction "IO34_6") (pintype "input"))
    )
    (net (code "9") (name "/DAC_O") (class "Default")
      (node (ref "R23") (pin "2") (pinfunction "2_2") (pintype "passive"))
      (node (ref "TP17") (pin "1") (pinfunction "1_1") (pintype "passive"))
      (node (ref "U4") (pin "11") (pinfunction "IO26_11") (pintype "bidirectional"))
    )
    (net (code "10") (name "/DAC_S") (class "Default")
      (node (ref "R24") (pin "2") (pinfunction "2_2") (pintype "passive"))
      (node (ref "TP20") (pin "1") (pinfunction "1_1") (pintype "passive"))
      (node (ref "U9") (pin "8") (pinfunction "VOUTA_8") (pintype "passive"))
    )
    (net (code "11") (name "/D_N") (class "Default")
      (node (ref "H2") (pin "2") (pinfunction "D-_2") (pintype "passive"))
      (node (ref "U3") (pin "12") (pinfunction "D-_12") (pintype "bidirectional"))
    )
    (net (code "12") (name "/D_P") (class "Default")
      (node (ref "H2") (pin "3") (pinfunction "D+_3") (pintype "passive"))
      (node (ref "U3") (pin "13") (pinfunction "D+_13") (pintype "bidirectional"))
    )
    (net (code "13") (name "/Debug") (class "Default")
      (node (ref "R33") (pin "2") (pinfunction "2_2") (pintype "passive"))
      (node (ref "U4") (pin "27") (pinfunction "IO16_27") (pintype "bidirectional"))
    )
    (net (code "15") (name "/EN1") (class "Default")
      (node (ref "U6") (pin "11") (pinfunction "Q0_11") (pintype "passive"))
    )
    (net (code "16") (name "/EN2") (class "Default")
      (node (ref "U6") (pin "10") (pinfunction "Q2_10") (pintype "passive"))
    )
    (net (code "17") (name "/EN3") (class "Default")
      (node (ref "U6") (pin "20") (pinfunction "Q10_20") (pintype "passive"))
    )
    (net (code "18") (name "/EN4") (class "Default")
      (node (ref "U6") (pin "17") (pinfunction "Q9_17") (pintype "passive"))
    )
    (net (code "19") (name "/EN5") (class "Default")
      (node (ref "U6") (pin "9") (pinfunction "Q1_9") (pintype "passive"))
    )
    (net (code "20") (name "/EN6") (class "Default")
      (node (ref "U6") (pin "19") (pinfunction "Q11_19") (pintype "passive"))
    )
    (net (code "21") (name "/EN7") (class "Default")
      (node (ref "U6") (pin "18") (pinfunction "Q8_18") (pintype "passive"))
    )
    (net (code "22") (name "/EN8") (class "Default")
      (node (ref "U6") (pin "8") (pinfunction "Q3_8") (pintype "passive"))
    )
    (net (code "23") (name "/EN9") (class "Default")
      (node (ref "U6") (pin "4") (pinfunction "Q7_4") (pintype "passive"))
    )
    (net (code "24") (name "/EN10") (class "Default")
      (node (ref "U6") (pin "7") (pinfunction "Q4_7") (pintype "passive"))
    )
    (net (code "25") (name "/EN11") (class "Default")
      (node (ref "U6") (pin "6") (pinfunction "Q5_6") (pintype "passive"))
    )
    (net (code "26") (name "/EN12") (class "Default")
      (node (ref "U6") (pin "5") (pinfunction "Q6_5") (pintype "passive"))
    )
    (net (code "28") (name "/F_EN") (class "Default")
      (node (ref "R13") (pin "2") (pinfunction "2_2") (pintype "passive"))
      (node (ref "R15") (pin "1") (pinfunction "1_1") (pintype "passive"))
      (node (ref "R25") (pin "2") (pinfunction "2_2") (pintype "passive"))
      (node (ref "U4") (pin "8") (pinfunction "IO32_8") (pintype "bidirectional"))
    )
    (net (code "29") (name "/LE") (class "Default")
      (node (ref "R35") (pin "2") (pinfunction "2_2") (pintype "passive"))
      (node (ref "U4") (pin "14") (pinfunction "IO12_14") (pintype "bidirectional"))
      (node (ref "U6") (pin "1") (pinfunction "LE_1") (pintype "passive"))
    )
    (net (code "30") (name "/MFP") (class "Default")
      (node (ref "R29") (pin "2") (pinfunction "2_2") (pintype "passive"))
      (node (ref "R37") (pin "1") (pinfunction "1_1") (pintype "passive"))
      (node (ref "TP19") (pin "1") (pinfunction "1_1") (pintype "passive"))
      (node (ref "U7") (pin "7") (pinfunction "MFP_7") (pintype "output"))
    )
    (net (code "31") (name "/MISO") (class "Default")
      (node (ref "TP12") (pin "1") (pinfunction "1_1") (pintype "passive"))
      (node (ref "U4") (pin "31") (pinfunction "IO19_31") (pintype "bidirectional"))
    )
    (net (code "32") (name "/MOSI") (class "Default")
      (node (ref "TP13") (pin "1") (pinfunction "1_1") (pintype "passive"))
      (node (ref "U4") (pin "37") (pinfunction "IO23_37") (pintype "bidirectional"))
      (node (ref "U9") (pin "4") (pinfunction "SDI_4") (pintype "passive"))
    )
    (net (code "33") (name "/Mode") (class "Default")
      (node (ref "C36") (pin "2") (pinfunction "2_2") (pintype "passive"))
      (node (ref "R32") (pin "1") (pinfunction "1_1") (pintype "passive"))
      (node (ref "SW3") (pin "2") (pintype "passive"))
      (node (ref "U4") (pin "4") (pinfunction "SENSOR_VP_4") (pintype "input"))
    )
    (net (code "34") (name "/RX") (class "Default")
      (node (ref "U3") (pin "5") (pinfunction "URX_5") (pintype "input"))
      (node (ref "U4") (pin "35") (pinfunction "TXD0_35") (pintype "bidirectional"))
    )
    (net (code "35") (name "/SCL") (class "Default")
      (node (ref "R19") (pin "1") (pinfunction "1_1") (pintype "passive"))
      (node (ref "TP15") (pin "1") (pinfunction "1_1") (pintype "passive"))
      (node (ref "U4") (pin "36") (pinfunction "IO22_36") (pintype "bidirectional"))
      (node (ref "U7") (pin "6") (pinfunction "SCL_6") (pintype "input"))
      (node (ref "U8") (pin "6") (pinfunction "SCL_6") (pintype "input"))
    )
    (net (code "36") (name "/SCLK") (class "Default")
      (node (ref "TP11") (pin "1") (pinfunction "1_1") (pintype "passive"))
      (node (ref "U4") (pin "30") (pinfunction "IO18_30") (pintype "bidirectional"))
      (node (ref "U9") (pin "3") (pinfunction "SCK_3") (pintype "passive"))
    )
    (net (code "37") (name "/SDA") (class "Default")
      (node (ref "R18") (pin "1") (pinfunction "1_1") (pintype "passive"))
      (node (ref "TP14") (pin "1") (pinfunction "1_1") (pintype "passive"))
      (node (ref "U4") (pin "33") (pinfunction "IO21_33") (pintype "bidirectional"))
      (node (ref "U7") (pin "5") (pinfunction "SDA_5") (pintype "bidirectional"))
      (node (ref "U8") (pin "5") (pinfunction "SDA_5") (pintype "bidirectional"))
    )
    (net (code "38") (name "/TX") (class "Default")
      (node (ref "U3") (pin "6") (pinfunction "UTX_6") (pintype "output"))
      (node (ref "U4") (pin "34") (pinfunction "RXD0_34") (pintype "bidirectional"))
    )
    (net (code "39") (name "/V_EN") (class "Default")
      (node (ref "R11") (pin "2") (pinfunction "2_2") (pintype "passive"))
      (node (ref "R12") (pin "2") (pinfunction "2_2") (pintype "passive"))
      (node (ref "U4") (pin "10") (pinfunction "IO25_10") (pintype "bidirectional"))
    )
    (net (code "40") (name "/V_OUT") (class "Default")
      (node (ref "R21") (pin "1") (pinfunction "1_1") (pintype "passive"))
      (node (ref "T1") (pin "6") (pinfunction "Ns_6") (pintype "passive"))
      (node (ref "TP18") (pin "1") (pinfunction "1_1") (pintype "passive"))
      (node (ref "U5") (pin "16") (pinfunction "OUTA_16") (pintype "passive"))
    )
    (net (code "41") (name "/Vref") (class "Default")
      (node (ref "C42") (pin "2") (pinfunction "2_2") (pintype "passive"))
      (node (ref "L3") (pin "2") (pinfunction "2_2") (pintype "passive"))
      (node (ref "U9") (pin "1") (pinfunction "VDD_1") (pintype "passive"))
      (node (ref "U9") (pin "6") (pinfunction "VREFA_6") (pintype "passive"))
    )
    (net (code "42") (name "/WP") (class "Default")
      (node (ref "R38") (pin "1") (pinfunction "1_1") (pintype "passive"))
      (node (ref "R41") (pin "2") (pinfunction "2_2") (pintype "passive"))
      (node (ref "U4") (pin "28") (pinfunction "IO17_28") (pintype "bidirectional"))
      (node (ref "U8") (pin "7") (pinfunction "WP_7") (pintype "input"))
    )
    (net (code "43") (name "/nCS") (class "Default")
      (node (ref "R39") (pin "1") (pinfunction "1_1") (pintype "passive"))
      (node (ref "TP8") (pin "1") (pinfunction "1_1") (pintype "passive"))
      (node (ref "U4") (pin "26") (pinfunction "IO4_26") (pintype "bidirectional"))
      (node (ref "U9") (pin "2") (pinfunction "nCS_2") (pintype "passive"))
    )
    (net (code "44") (name "/nE") (class "Default")
      (node (ref "R34") (pin "1") (pinfunction "1_1") (pintype "passive"))
      (node (ref "U4") (pin "13") (pinfunction "IO14_13") (pintype "bidirectional"))
      (node (ref "U6") (pin "23") (pinfunction "~{E}_23") (pintype "passive"))
    )
    (net (code "45") (name "/nLDAC") (class "Default")
      (node (ref "R40") (pin "1") (pinfunction "1_1") (pintype "passive"))
      (node (ref "U4") (pin "29") (pinfunction "IO5_29") (pintype "bidirectional"))
      (node (ref "U9") (pin "5") (pinfunction "nLDAC_5") (pintype "passive"))
    )
    (net (code "46") (name "3V3") (class "Default")
      (node (ref "C1") (pin "2") (pinfunction "2_2") (pintype "passive"))
      (node (ref "C16") (pin "2") (pinfunction "2_2") (pintype "passive"))
      (node (ref "C17") (pin "1") (pinfunction "1_1") (pintype "passive"))
      (node (ref "C2") (pin "2") (pinfunction "2_2") (pintype "passive"))
      (node (ref "C22") (pin "2") (pinfunction "2_2") (pintype "passive"))
      (node (ref "C23") (pin "2") (pinfunction "2_2") (pintype "passive"))
      (node (ref "C37") (pin "2") (pinfunction "2_2") (pintype "passive"))
      (node (ref "C39") (pin "2") (pinfunction "2_2") (pintype "passive"))
      (node (ref "C41") (pin "2") (pinfunction "2_2") (pintype "passive"))
      (node (ref "H4") (pin "1") (pinfunction "3V3_1") (pintype "passive"))
      (node (ref "L3") (pin "1") (pinfunction "1_1") (pintype "passive"))
      (node (ref "R14") (pin "1") (pinfunction "1_1") (pintype "passive"))
      (node (ref "R16") (pin "1") (pinfunction "1_1") (pintype "passive"))
      (node (ref "R17") (pin "1") (pinfunction "1_1") (pintype "passive"))
      (node (ref "R18") (pin "2") (pinfunction "2_2") (pintype "passive"))
      (node (ref "R19") (pin "2") (pinfunction "2_2") (pintype "passive"))
      (node (ref "R30") (pin "2") (pinfunction "2_2") (pintype "passive"))
      (node (ref "R31") (pin "2") (pinfunction "2_2") (pintype "passive"))
      (node (ref "R32") (pin "2") (pinfunction "2_2") (pintype "passive"))
      (node (ref "R34") (pin "2") (pinfunction "2_2") (pintype "passive"))
      (node (ref "R37") (pin "2") (pinfunction "2_2") (pintype "passive"))
      (node (ref "R38") (pin "2") (pinfunction "2_2") (pintype "passive"))
      (node (ref "R39") (pin "2") (pinfunction "2_2") (pintype "passive"))
      (node (ref "R40") (pin "2") (pinfunction "2_2") (pintype "passive"))
      (node (ref "TP1") (pin "1") (pinfunction "1_1") (pintype "passive"))
      (node (ref "U1") (pin "5") (pinfunction "VOUT_5") (pintype "passive"))
      (node (ref "U3") (pin "1") (pinfunction "VDD_1") (pintype "power_in"))
      (node (ref "U3") (pin "11") (pinfunction "VUSB_11") (pintype "power_in"))
      (node (ref "U4") (pin "2") (pinfunction "3V3_2") (pintype "power_in"))
      (node (ref "U6") (pin "24") (pinfunction "VCC_24") (pintype "passive"))
      (node (ref "U7") (pin "8") (pinfunction "VCC_8") (pintype "power_in"))
      (node (ref "U8") (pin "8") (pinfunction "VCC_8") (pintype "power_in"))
    )
    (net (code "47") (name "5V") (class "Default")
      (node (ref "C14") (pin "2") (pinfunction "2_2") (pintype "passive"))
      (node (ref "C3") (pin "1") (pinfunction "1_1") (pintype "passive"))
      (node (ref "C4") (pin "1") (pinfunction "1_1") (pintype "passive"))
      (node (ref "C5") (pin "2") (pinfunction "2_2") (pintype "passive"))
      (node (ref "C6") (pin "2") (pinfunction "2_2") (pintype "passive"))
      (node (ref "C7") (pin "2") (pinfunction "2_2") (pintype "passive"))
      (node (ref "F1") (pin "2") (pinfunction "2_2") (pintype "passive"))
      (node (ref "Q1") (pin "2") (pinfunction "S_2") (pintype "passive"))
      (node (ref "Q2") (pin "2") (pinfunction "2_2") (pintype "passive"))
      (node (ref "R6") (pin "2") (pinfunction "2_2") (pintype "passive"))
      (node (ref "R9") (pin "1") (pinfunction "1_1") (pintype "passive"))
      (node (ref "TP2") (pin "1") (pinfunction "1_1") (pintype "passive"))
      (node (ref "U1") (pin "1") (pinfunction "VIN_1") (pintype "power_in"))
      (node (ref "U1") (pin "3") (pinfunction "EN_3") (pintype "passive"))
      (node (ref "U2") (pin "5") (pinfunction "INN_5_5") (pintype "input"))
      (node (ref "U2") (pin "6") (pinfunction "INN_6_6") (pintype "input"))
    )
    (net (code "48") (name "GND") (class "Default")
      (node (ref "C1") (pin "1") (pinfunction "1_1") (pintype "passive"))
      (node (ref "C12") (pin "2") (pinfunction "2_2") (pintype "passive"))
      (node (ref "C14") (pin "1") (pinfunction "1_1") (pintype "passive"))
      (node (ref "C15") (pin "1") (pinfunction "1_1") (pintype "passive"))
      (node (ref "C16") (pin "1") (pinfunction "1_1") (pintype "passive"))
      (node (ref "C17") (pin "2") (pinfunction "2_2") (pintype "passive"))
      (node (ref "C18") (pin "1") (pinfunction "1_1") (pintype "passive"))
      (node (ref "C19") (pin "1") (pinfunction "1_1") (pintype "passive"))
      (node (ref "C2") (pin "1") (pinfunction "1_1") (pintype "passive"))
      (node (ref "C20") (pin "1") (pinfunction "1_1") (pintype "passive"))
      (node (ref "C21") (pin "1") (pinfunction "1_1") (pintype "passive"))
      (node (ref "C22") (pin "1") (pinfunction "1_1") (pintype "passive"))
      (node (ref "C23") (pin "1") (pinfunction "1_1") (pintype "passive"))
      (node (ref "C24") (pin "1") (pinfunction "1_1") (pintype "passive"))
      (node (ref "C25") (pin "1") (pinfunction "1_1") (pintype "passive"))
      (node (ref "C26") (pin "1") (pinfunction "1_1") (pintype "passive"))
      (node (ref "C27") (pin "1") (pinfunction "1_1") (pintype "passive"))
      (node (ref "C28") (pin "1") (pinfunction "1_1") (pintype "passive"))
      (node (ref "C29") (pin "1") (pinfunction "1_1") (pintype "passive"))
      (node (ref "C3") (pin "2") (pinfunction "2_2") (pintype "passive"))
      (node (ref "C30") (pin "1") (pinfunction "1_1") (pintype "passive"))
      (node (ref "C31") (pin "1") (pinfunction "1_1") (pintype "passive"))
      (node (ref "C32") (pin "1") (pinfunction "1_1") (pintype "passive"))
      (node (ref "C33") (pin "1") (pinfunction "1_1") (pintype "passive"))
      (node (ref "C34") (pin "1") (pinfunction "1_1") (pintype "passive"))
      (node (ref "C35") (pin "1") (pinfunction "1_1") (pintype "passive"))
      (node (ref "C36") (pin "1") (pinfunction "1_1") (pintype "passive"))
      (node (ref "C37") (pin "1") (pinfunction "1_1") (pintype "passive"))
      (node (ref "C38") (pin "1") (pinfunction "1_1") (pintype "passive"))
      (node (ref "C39") (pin "1") (pinfunction "1_1") (pintype "passive"))
      (node (ref "C4") (pin "2") (pinfunction "2_2") (pintype "passive"))
      (node (ref "C40") (pin "1") (pinfunction "1_1") (pintype "passive"))
      (node (ref "C41") (pin "1") (pinfunction "1_1") (pintype "passive"))
      (node (ref "C42") (pin "1") (pinfunction "1_1") (pintype "passive"))
      (node (ref "C5") (pin "1") (pinfunction "1_1") (pintype "passive"))
      (node (ref "C6") (pin "1") (pinfunction "1_1") (pintype "passive"))
      (node (ref "C7") (pin "1") (pinfunction "1_1") (pintype "passive"))
      (node (ref "C8") (pin "1") (pinfunction "1_1") (pintype "passive"))
      (node (ref "C9") (pin "1") (pinfunction "1_1") (pintype "passive"))
      (node (ref "D3") (pin "2") (pinfunction "2_2") (pintype "passive"))
      (node (ref "D4") (pin "2") (pinfunction "2_2") (pintype "passive"))
      (node (ref "DL3") (pin "1") (pinfunction "K_1") (pintype "passive"))
      (node (ref "H1") (pin "1") (pinfunction "GND_1") (pintype "passive"))
      (node (ref "H1") (pin "3") (pinfunction "GND_3") (pintype "passive"))
      (node (ref "H2") (pin "GND") (pinfunction "GND_GND") (pintype "passive"))
      (node (ref "H3") (pin "2") (pinfunction "N_2") (pintype "passive"))
      (node (ref "H4") (pin "3") (pinfunction "GND_3") (pintype "passive"))
      (node (ref "H5") (pin "1") (pinfunction "GND_1") (pintype "passive"))
      (node (ref "H6") (pin "2") (pinfunction "N_2") (pintype "passive"))
      (node (ref "L2") (pin "1") (pinfunction "1_1") (pintype "passive"))
      (node (ref "MH1") (pin "1") (pinfunction "1_1") (pintype "passive"))
      (node (ref "MH2") (pin "1") (pinfunction "1_1") (pintype "passive"))
      (node (ref "MH3") (pin "1") (pinfunction "1_1") (pintype "passive"))
      (node (ref "MH4") (pin "1") (pinfunction "1_1") (pintype "passive"))
      (node (ref "MH5") (pin "1") (pinfunction "1_1") (pintype "passive"))
      (node (ref "MH6") (pin "1") (pinfunction "1_1") (pintype "passive"))
      (node (ref "Q3") (pin "2") (pinfunction "2_2") (pintype "passive"))
      (node (ref "R12") (pin "1") (pinfunction "1_1") (pintype "passive"))
      (node (ref "R15") (pin "2") (pinfunction "2_2") (pintype "passive"))
      (node (ref "R28") (pin "2") (pinfunction "2_2") (pintype "passive"))
      (node (ref "R35") (pin "1") (pinfunction "1_1") (pintype "passive"))
      (node (ref "R36") (pin "1") (pinfunction "1_1") (pintype "passive"))
      (node (ref "R41") (pin "1") (pinfunction "1_1") (pintype "passive"))
      (node (ref "R5") (pin "2") (pinfunction "2_2") (pintype "passive"))
      (node (ref "SW1") (pin "2") (pintype "passive"))
      (node (ref "SW2") (pin "1") (pintype "passive"))
      (node (ref "SW3") (pin "1") (pintype "passive"))
      (node (ref "T1") (pin "4") (pinfunction "4_4") (pintype "passive"))
      (node (ref "TP3") (pin "1") (pinfunction "1_1") (pintype "passive"))
      (node (ref "TP4") (pin "1") (pinfunction "1_1") (pintype "passive"))
      (node (ref "TP5") (pin "1") (pinfunction "1_1") (pintype "passive"))
      (node (ref "U1") (pin "2") (pinfunction "GND_2") (pintype "power_in"))
      (node (ref "U2") (pin "25") (pinfunction "GND_25") (pintype "passive"))
      (node (ref "U3") (pin "14") (pinfunction "VSS_14") (pintype "power_in"))
      (node (ref "U4") (pin "1") (pinfunction "GND_1") (pintype "power_in"))
      (node (ref "U5") (pin "A0") (pinfunction "A0_A0") (pintype "passive"))
      (node (ref "U5") (pin "A1") (pinfunction "A1_A1") (pintype "passive"))
      (node (ref "U5") (pin "GND") (pinfunction "GND_GND") (pintype "power_in"))
      (node (ref "U6") (pin "12") (pinfunction "GND_12") (pintype "passive"))
      (node (ref "U7") (pin "4") (pinfunction "GND_4") (pintype "power_in"))
      (node (ref "U8") (pin "1") (pinfunction "A0_1") (pintype "input"))
      (node (ref "U8") (pin "2") (pinfunction "A1_2") (pintype "input"))
      (node (ref "U8") (pin "3") (pinfunction "A2_3") (pintype "input"))
      (node (ref "U8") (pin "4") (pinfunction "VSS_4") (pintype "power_in"))
      (node (ref "U9") (pin "7") (pinfunction "GND_7") (pintype "passive"))
    )
    (net (code "49") (name "N") (class "Default")
      (node (ref "T2") (pin "3") (pinfunction "3_3") (pintype "passive"))
      (node (ref "TP10") (pin "1") (pinfunction "1_1") (pintype "passive"))
    )
    (net (code "50") (name "Net-(C27-Pad2)") (class "Default")
      (node (ref "C27") (pin "2") (pinfunction "2_2") (pintype "passive"))
      (node (ref "R25") (pin "1") (pinfunction "1_1") (pintype "passive"))
      (node (ref "Y1") (pin "1") (pinfunction "1_1") (pintype "passive"))
    )
    (net (code "51") (name "Net-(C33-Pad2)") (class "Default")
      (node (ref "C33") (pin "2") (pinfunction "2_2") (pintype "passive"))
      (node (ref "R26") (pin "1") (pinfunction "1_1") (pintype "passive"))
      (node (ref "Y1") (pin "2") (pinfunction "2_2") (pintype "passive"))
    )
    (net (code "52") (name "Net-(D1-A)") (class "Default")
      (node (ref "D1") (pin "2") (pinfunction "A_2") (pintype "passive"))
      (node (ref "L1") (pin "2") (pinfunction "2_2") (pintype "passive"))
      (node (ref "U2") (pin "1") (pinfunction "INP_1_1") (pintype "input"))
      (node (ref "U2") (pin "24") (pinfunction "INP_24_24") (pintype "input"))
    )
    (net (code "53") (name "Net-(D2-K)") (class "Default")
      (node (ref "D2") (pin "1") (pinfunction "K_1") (pintype "passive"))
      (node (ref "L2") (pin "2") (pinfunction "2_2") (pintype "passive"))
      (node (ref "U2") (pin "13") (pinfunction "OUTN_13_13") (pintype "output"))
      (node (ref "U2") (pin "14") (pinfunction "OUTN_14_14") (pintype "output"))
    )
    (net (code "54") (name "Net-(DL1-A)") (class "Default")
      (node (ref "DL1") (pin "2") (pinfunction "A_2") (pintype "passive"))
      (node (ref "R14") (pin "2") (pinfunction "2_2") (pintype "passive"))
    )
    (net (code "55") (name "Net-(DL1-K)") (class "Default")
      (node (ref "DL1") (pin "1") (pinfunction "K_1") (pintype "passive"))
      (node (ref "U3") (pin "2") (pinfunction "GP0_2") (pintype "bidirectional"))
    )
    (net (code "56") (name "Net-(DL2-A)") (class "Default")
      (node (ref "DL2") (pin "2") (pinfunction "A_2") (pintype "passive"))
      (node (ref "R16") (pin "2") (pinfunction "2_2") (pintype "passive"))
    )
    (net (code "57") (name "Net-(DL2-K)") (class "Default")
      (node (ref "DL2") (pin "1") (pinfunction "K_1") (pintype "passive"))
      (node (ref "U3") (pin "3") (pinfunction "GP1_3") (pintype "bidirectional"))
    )
    (net (code "58") (name "Net-(DL3-A)") (class "Default")
      (node (ref "DL3") (pin "2") (pinfunction "A_2") (pintype "passive"))
      (node (ref "H6") (pin "1") (pinfunction "P_1") (pintype "passive"))
      (node (ref "R33") (pin "1") (pinfunction "1_1") (pintype "passive"))
    )
    (net (code "59") (name "Net-(H1-+5V)") (class "Default")
      (node (ref "F1") (pin "1") (pinfunction "1_1") (pintype "passive"))
      (node (ref "H1") (pin "2") (pinfunction "+5V_2") (pintype "passive"))
    )
    (net (code "60") (name "Net-(H3-P)") (class "Default")
      (node (ref "C21") (pin "2") (pinfunction "2_2") (pintype "passive"))
      (node (ref "D3") (pin "1") (pinfunction "1_1") (pintype "passive"))
      (node (ref "H3") (pin "1") (pinfunction "P_1") (pintype "passive"))
      (node (ref "Q2") (pin "3") (pinfunction "3_3") (pintype "passive"))
    )
    (net (code "61") (name "Net-(H4-V_INT)") (class "Default")
      (node (ref "H4") (pin "2") (pinfunction "V_INT_2") (pintype "passive"))
      (node (ref "R22") (pin "1") (pinfunction "1_1") (pintype "passive"))
    )
    (net (code "62") (name "Net-(Q1-D)") (class "Default")
      (node (ref "C8") (pin "2") (pinfunction "2_2") (pintype "passive"))
      (node (ref "L1") (pin "1") (pinfunction "1_1") (pintype "passive"))
      (node (ref "Q1") (pin "3") (pinfunction "D_3") (pintype "passive"))
    )
    (net (code "63") (name "Net-(Q1-G)") (class "Default")
      (node (ref "Q1") (pin "1") (pinfunction "G_1") (pintype "passive"))
      (node (ref "U2") (pin "7") (pinfunction "BSW_7") (pintype "output"))
    )
    (net (code "64") (name "Net-(Q2-Pad1)") (class "Default")
      (node (ref "Q2") (pin "1") (pinfunction "1_1") (pintype "passive"))
      (node (ref "Q3") (pin "3") (pinfunction "3_3") (pintype "passive"))
      (node (ref "R9") (pin "2") (pinfunction "2_2") (pintype "passive"))
    )
    (net (code "65") (name "Net-(Q3-Pad1)") (class "Default")
      (node (ref "Q3") (pin "1") (pinfunction "1_1") (pintype "passive"))
      (node (ref "R13") (pin "1") (pinfunction "1_1") (pintype "passive"))
    )
    (net (code "66") (name "Net-(R1-Pad2)") (class "Default")
      (node (ref "R1") (pin "2") (pinfunction "2_2") (pintype "passive"))
      (node (ref "R2") (pin "2") (pinfunction "2_2") (pintype "passive"))
    )
    (net (code "67") (name "Net-(R2-Pad1)") (class "Default")
      (node (ref "R2") (pin "1") (pinfunction "1_1") (pintype "passive"))
      (node (ref "R3") (pin "1") (pinfunction "1_1") (pintype "passive"))
    )
    (net (code "68") (name "Net-(R7-Pad2)") (class "Default")
      (node (ref "R7") (pin "2") (pinfunction "2_2") (pintype "passive"))
      (node (ref "R8") (pin "2") (pinfunction "2_2") (pintype "passive"))
    )
    (net (code "69") (name "Net-(R20-Pad1)") (class "Default")
      (node (ref "R20") (pin "1") (pinfunction "1_1") (pintype "passive"))
      (node (ref "R21") (pin "2") (pinfunction "2_2") (pintype "passive"))
    )
    (net (code "70") (name "Net-(R27-Pad1)") (class "Default")
      (node (ref "R27") (pin "1") (pinfunction "1_1") (pintype "passive"))
      (node (ref "R28") (pin "1") (pinfunction "1_1") (pintype "passive"))
    )
    (net (code "71") (name "Net-(T1-Np)") (class "Default")
      (node (ref "T1") (pin "1") (pinfunction "Np_1") (pintype "passive"))
      (node (ref "T2") (pin "6") (pinfunction "Ns_6") (pintype "passive"))
    )
    (net (code "72") (name "Net-(T1-Pad3)") (class "Default")
      (node (ref "T1") (pin "3") (pinfunction "3_3") (pintype "passive"))
      (node (ref "T2") (pin "4") (pinfunction "4_4") (pintype "passive"))
    )
    (net (code "73") (name "Net-(U2-CN)") (class "Default")
      (node (ref "C19") (pin "2") (pinfunction "2_2") (pintype "passive"))
      (node (ref "U2") (pin "18") (pinfunction "CN_18") (pintype "bidirectional"))
    )
    (net (code "74") (name "Net-(U2-CP)") (class "Default")
      (node (ref "C18") (pin "2") (pinfunction "2_2") (pintype "passive"))
      (node (ref "U2") (pin "21") (pinfunction "CP_21") (pintype "bidirectional"))
    )
    (net (code "75") (name "Net-(U2-ENN)") (class "Default")
      (node (ref "R10") (pin "1") (pinfunction "1_1") (pintype "passive"))
      (node (ref "R11") (pin "1") (pinfunction "1_1") (pintype "passive"))
      (node (ref "U2") (pin "10") (pinfunction "ENN_10") (pintype "input"))
      (node (ref "U2") (pin "11") (pinfunction "PSN_11") (pintype "input"))
      (node (ref "U2") (pin "8") (pinfunction "ENP_8") (pintype "input"))
      (node (ref "U2") (pin "9") (pinfunction "PSP_9") (pintype "input"))
    )
    (net (code "76") (name "Net-(U2-FBN)") (class "Default")
      (node (ref "C13") (pin "2") (pinfunction "2_2") (pintype "passive"))
      (node (ref "R4") (pin "2") (pinfunction "2_2") (pintype "passive"))
      (node (ref "R7") (pin "1") (pinfunction "1_1") (pintype "passive"))
      (node (ref "U2") (pin "16") (pinfunction "FBN_16") (pintype "input"))
    )
    (net (code "77") (name "Net-(U2-FBP)") (class "Default")
      (node (ref "C10") (pin "1") (pinfunction "1_1") (pintype "passive"))
      (node (ref "C11") (pin "1") (pinfunction "1_1") (pintype "passive"))
      (node (ref "R3") (pin "2") (pinfunction "2_2") (pintype "passive"))
      (node (ref "R5") (pin "1") (pinfunction "1_1") (pintype "passive"))
      (node (ref "U2") (pin "22") (pinfunction "FBP_22") (pintype "input"))
    )
    (net (code "78") (name "Net-(U2-VIN)") (class "Default")
      (node (ref "C15") (pin "2") (pinfunction "2_2") (pintype "passive"))
      (node (ref "R10") (pin "2") (pinfunction "2_2") (pintype "passive"))
      (node (ref "R6") (pin "1") (pinfunction "1_1") (pintype "passive"))
      (node (ref "U2") (pin "4") (pinfunction "VIN_4") (pintype "input"))
    )
    (net (code "79") (name "Net-(U2-VREF)") (class "Default")
      (node (ref "C12") (pin "1") (pinfunction "1_1") (pintype "passive"))
      (node (ref "R4") (pin "1") (pinfunction "1_1") (pintype "passive"))
      (node (ref "U2") (pin "17") (pinfunction "VREF_17") (pintype "output"))
    )
    (net (code "80") (name "Net-(U4-EN)") (class "Default")
      (node (ref "C25") (pin "2") (pinfunction "2_2") (pintype "passive"))
      (node (ref "C26") (pin "2") (pinfunction "2_2") (pintype "passive"))
      (node (ref "R17") (pin "2") (pinfunction "2_2") (pintype "passive"))
      (node (ref "SW2") (pin "2") (pintype "passive"))
      (node (ref "U4") (pin "3") (pinfunction "EN_3") (pintype "input"))
    )
    (net (code "81") (name "Net-(U4-IO0)") (class "Default")
      (node (ref "C24") (pin "2") (pinfunction "2_2") (pintype "passive"))
      (node (ref "SW1") (pin "1") (pintype "passive"))
      (node (ref "U4") (pin "25") (pinfunction "IO0_25") (pintype "bidirectional"))
    )
    (net (code "82") (name "Net-(U4-IO33)") (class "Default")
      (node (ref "R26") (pin "2") (pinfunction "2_2") (pintype "passive"))
      (node (ref "R29") (pin "1") (pinfunction "1_1") (pintype "passive"))
      (node (ref "U4") (pin "9") (pinfunction "IO33_9") (pintype "bidirectional"))
    )
    (net (code "83") (name "Net-(U4-IO35)") (class "Default")
      (node (ref "C28") (pin "2") (pinfunction "2_2") (pintype "passive"))
      (node (ref "D4") (pin "1") (pinfunction "1_1") (pintype "passive"))
      (node (ref "R22") (pin "2") (pinfunction "2_2") (pintype "passive"))
      (node (ref "TP16") (pin "1") (pinfunction "1_1") (pintype "passive"))
      (node (ref "U4") (pin "7") (pinfunction "IO35_7") (pintype "input"))
    )
    (net (code "84") (name "Net-(U5A-IN+)") (class "Default")
      (node (ref "R23") (pin "1") (pinfunction "1_1") (pintype "passive"))
      (node (ref "R27") (pin "2") (pinfunction "2_2") (pintype "passive"))
      (node (ref "U5") (pin "3") (pinfunction "IN+_3") (pintype "tri_state"))
    )
    (net (code "85") (name "Net-(U5A-IN-)") (class "Default")
      (node (ref "R20") (pin "2") (pinfunction "2_2") (pintype "passive"))
      (node (ref "R24") (pin "1") (pinfunction "1_1") (pintype "passive"))
      (node (ref "U5") (pin "2") (pinfunction "IN-_2") (pintype "tri_state"))
    )
    (net (code "86") (name "Net-(U7-X1)") (class "Default")
      (node (ref "C38") (pin "2") (pinfunction "2_2") (pintype "passive"))
      (node (ref "U7") (pin "1") (pinfunction "X1_1") (pintype "input"))
      (node (ref "Y2") (pin "2") (pinfunction "2_2") (pintype "passive"))
    )
    (net (code "87") (name "Net-(U7-X2)") (class "Default")
      (node (ref "C40") (pin "2") (pinfunction "2_2") (pintype "passive"))
      (node (ref "U7") (pin "2") (pinfunction "X2_2") (pintype "output"))
      (node (ref "Y2") (pin "1") (pinfunction "1_1") (pintype "passive"))
    )
    (net (code "88") (name "P") (class "Default")
      (node (ref "T2") (pin "1") (pinfunction "Np_1") (pintype "passive"))
      (node (ref "TP9") (pin "1") (pinfunction "1_1") (pintype "passive"))
    )
    (net (code "89") (name "unconnected-(H2-ID-Pad4)") (class "Default")
      (node (ref "H2") (pin "4") (pinfunction "ID_4") (pintype "power_in+no_connect"))
    )
    (net (code "90") (name "unconnected-(H2-VBUS-Pad1)") (class "Default")
      (node (ref "H2") (pin "1") (pinfunction "VBUS_1") (pintype "power_in+no_connect"))
    )
    (net (code "91") (name "unconnected-(U1-NC-Pad4)") (class "Default")
      (node (ref "U1") (pin "4") (pinfunction "NC_4") (pintype "passive+no_connect"))
    )
    (net (code "92") (name "unconnected-(U3-GP2-Pad7)") (class "Default")
      (node (ref "U3") (pin "7") (pinfunction "GP2_7") (pintype "bidirectional"))
    )
    (net (code "93") (name "unconnected-(U3-GP3-Pad8)") (class "Default")
      (node (ref "U3") (pin "8") (pinfunction "GP3_8") (pintype "bidirectional"))
    )
    (net (code "94") (name "unconnected-(U3-SCL-Pad10)") (class "Default")
      (node (ref "U3") (pin "10") (pinfunction "SCL_10") (pintype "bidirectional+no_connect"))
    )
    (net (code "95") (name "unconnected-(U3-SDA-Pad9)") (class "Default")
      (node (ref "U3") (pin "9") (pinfunction "SDA_9") (pintype "bidirectional+no_connect"))
    )
    (net (code "96") (name "unconnected-(U3-~{RST}-Pad4)") (class "Default")
      (node (ref "U3") (pin "4") (pinfunction "~{RST}_4") (pintype "input+no_connect"))
    )
    (net (code "97") (name "unconnected-(U5B-IN+-Pad10)") (class "Default")
      (node (ref "U5") (pin "10") (pinfunction "IN+_10") (pintype "tri_state+no_connect"))
    )
    (net (code "98") (name "unconnected-(U5B-IN--Pad11)") (class "Default")
      (node (ref "U5") (pin "11") (pinfunction "IN-_11") (pintype "tri_state+no_connect"))
    )
    (net (code "99") (name "unconnected-(U5B-OUTA-Pad13)") (class "Default")
      (node (ref "U5") (pin "13") (pinfunction "OUTA_13") (pintype "passive+no_connect"))
    )
    (net (code "100") (name "unconnected-(U6-Q12-Pad14)") (class "Default")
      (node (ref "U6") (pin "14") (pinfunction "Q12_14") (pintype "passive+no_connect"))
    )
    (net (code "101") (name "unconnected-(U6-Q13-Pad13)") (class "Default")
      (node (ref "U6") (pin "13") (pinfunction "Q13_13") (pintype "passive+no_connect"))
    )
    (net (code "102") (name "unconnected-(U6-Q14-Pad16)") (class "Default")
      (node (ref "U6") (pin "16") (pinfunction "Q14_16") (pintype "passive+no_connect"))
    )
    (net (code "103") (name "unconnected-(U6-Q15-Pad15)") (class "Default")
      (node (ref "U6") (pin "15") (pinfunction "Q15_15") (pintype "passive+no_connect"))
    )
  )
)
